# Sheet1.net
KiCad netlist of a schematic drawn in Altium Designer
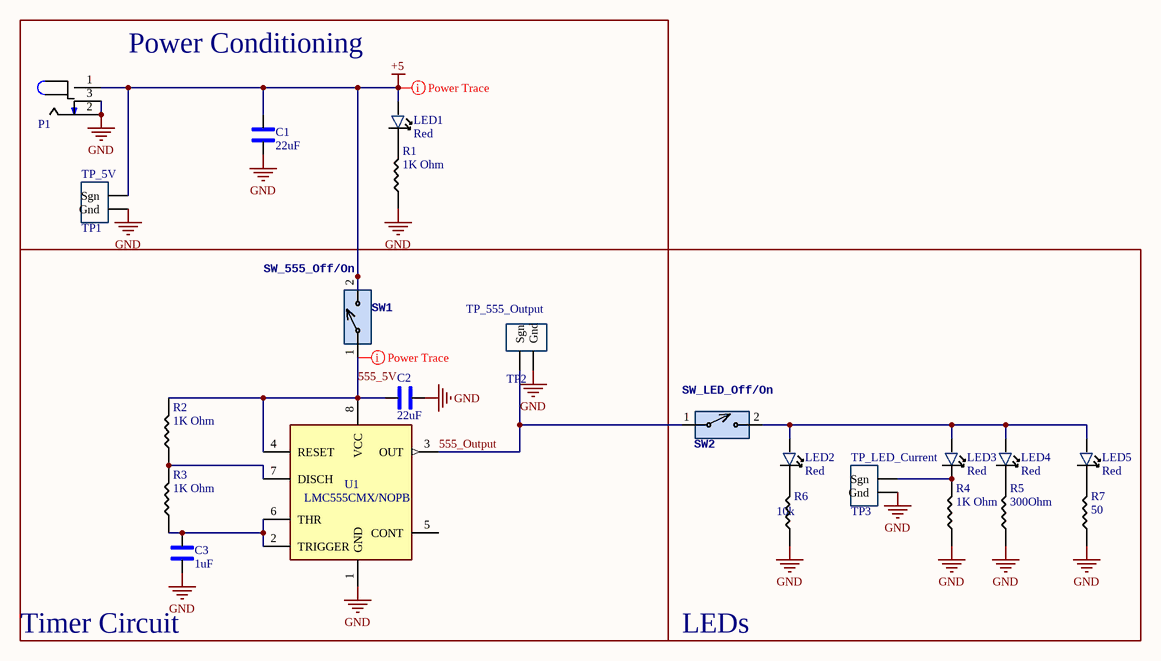
[diagram p0: Sheet1.SchDoc]

(export (version "E")
  (design (tool "Eeschema 10.0.6"))
  (components
    (comp (ref "C1")
      (value "22uF")
      (footprint "1206_Passive_Capacitor")
      (description "22uF ±10% 25V X5R 1206 Multilayer Ceramic Capacitors MLCC - SMD/SMT RoHS")
      (fields (field (name "MFR PART #") "CL31A226KAHNNNE") (field (name "LCSC PART#") "C12891"))
      (libsource (lib "ECEN5730Lib_2023_01_DS") (part "C_22uF_1206"))
    )
    (comp (ref "C2")
      (value "22uF")
      (footprint "1206_Passive_Capacitor")
      (description "22uF ±10% 25V X5R 1206 Multilayer Ceramic Capacitors MLCC - SMD/SMT RoHS")
      (fields (field (name "MFR PART #") "CL31A226KAHNNNE") (field (name "LCSC PART#") "C12891"))
      (libsource (lib "ECEN5730Lib_2023_01_DS") (part "C_22uF_1206"))
    )
    (comp (ref "C3")
      (value "1uF")
      (footprint "1206_Passive_Capacitor")
      (description "MULTILAYER CERAMIC CAPACITORS MLCC - SMD/SMT 1UF 50V 1206 ROHS")
      (fields (field (name "MFR PART #") "CL31B105KBHNNNE") (field (name "LCSC PART#") "C1848"))
      (libsource (lib "ECEN5730Lib_2023_01_DS") (part "C_1uF_1206"))
    )
    (comp (ref "LED1")
      (value "Red")
      (footprint "LED_1206")
      (description "Red 621~631nm 1206 Light Emitting Diodes (LED) RoHS")
      (fields (field (name "MFR PART #") "15-21/R6C-FQ1R1B/2T") (field (name "LCSC PART#") "C93133"))
      (libsource (lib "ECEN5730Lib_2023_01_DS") (part "LED_RED_1206"))
    )
    (comp (ref "LED2")
      (value "Red")
      (footprint "LED_1206")
      (description "Red 621~631nm 1206 Light Emitting Diodes (LED) RoHS")
      (fields (field (name "MFR PART #") "15-21/R6C-FQ1R1B/2T") (field (name "LCSC PART#") "C93133"))
      (libsource (lib "ECEN5730Lib_2023_01_DS") (part "LED_RED_1206"))
    )
    (comp (ref "LED3")
      (value "Red")
      (footprint "LED_1206")
      (description "Red 621~631nm 1206 Light Emitting Diodes (LED) RoHS")
      (fields (field (name "MFR PART #") "15-21/R6C-FQ1R1B/2T") (field (name "LCSC PART#") "C93133"))
      (libsource (lib "ECEN5730Lib_2023_01_DS") (part "LED_RED_1206"))
    )
    (comp (ref "LED4")
      (value "Red")
      (footprint "LED_1206")
      (description "Red 621~631nm 1206 Light Emitting Diodes (LED) RoHS")
      (fields (field (name "MFR PART #") "15-21/R6C-FQ1R1B/2T") (field (name "LCSC PART#") "C93133"))
      (libsource (lib "ECEN5730Lib_2023_01_DS") (part "LED_RED_1206"))
    )
    (comp (ref "LED5")
      (value "Red")
      (footprint "LED_1206")
      (description "Red 621~631nm 1206 Light Emitting Diodes (LED) RoHS")
      (fields (field (name "MFR PART #") "15-21/R6C-FQ1R1B/2T") (field (name "LCSC PART#") "C93133"))
      (libsource (lib "ECEN5730Lib_2023_01_DS") (part "LED_RED_1206"))
    )
    (comp (ref "P1")
      (value "Power Jack")
      (footprint "Power_Jack")
      (description "Power Barrel Connector Jack 2.10mm ID (0.083\"), 5.50mm OD (0.217\") Through Hole, Right Angle")
      (fields (field (name "MFR PART #") "PJ-102A") (field (name "LCSC PART#") "C136744"))
      (libsource (lib "ECEN5730Lib_2023_01_DS") (part "P_Power Jack"))
    )
    (comp (ref "R1")
      (value "1K Ohm")
      (footprint "1206_Passive_Resitor")
      (description "CHIP RESISTOR - SURFACE MOUNT 1KOHMS ±1% 1/4W 1206 ROHS")
      (fields (field (name "MFR PART #") "RNCP1206FTD1K00CT") (field (name "LCSC PART#") "C4410"))
      (libsource (lib "ECEN5730Lib_2023_01_DS") (part "R_1K_1206"))
    )
    (comp (ref "R2")
      (value "1K Ohm")
      (footprint "1206_Passive_Resitor")
      (description "CHIP RESISTOR - SURFACE MOUNT 1KOHMS ±1% 1/4W 1206 ROHS")
      (fields (field (name "MFR PART #") "RNCP1206FTD1K00CT") (field (name "LCSC PART#") "C4410"))
      (libsource (lib "ECEN5730Lib_2023_01_DS") (part "R_1K_1206"))
    )
    (comp (ref "R3")
      (value "1K Ohm")
      (footprint "1206_Passive_Resitor")
      (description "CHIP RESISTOR - SURFACE MOUNT 1KOHMS ±1% 1/4W 1206 ROHS")
      (fields (field (name "MFR PART #") "RNCP1206FTD1K00CT") (field (name "LCSC PART#") "C4410"))
      (libsource (lib "ECEN5730Lib_2023_01_DS") (part "R_1K_1206"))
    )
    (comp (ref "R4")
      (value "1K Ohm")
      (footprint "1206_Passive_Resitor")
      (description "CHIP RESISTOR - SURFACE MOUNT 1KOHMS ±1% 1/4W 1206 ROHS")
      (fields (field (name "MFR PART #") "RNCP1206FTD1K00CT") (field (name "LCSC PART#") "C4410"))
      (libsource (lib "ECEN5730Lib_2023_01_DS") (part "R_1K_1206"))
    )
    (comp (ref "R5")
      (value "300Ohm")
      (footprint "1206_Passive_Resitor")
      (description "CHIP RESISTOR - SURFACE MOUNT 300OHMS ±1% 1/4W 1206 ROHS")
      (fields (field (name "MFR PART #") "1206W4F3000T5E") (field (name "LCSC PART#") "C17887"))
      (libsource (lib "ECEN5730Lib_2023_01_DS") (part "R_300Ohm_1206"))
    )
    (comp (ref "R6")
      (value "10k")
      (footprint "1206_Passive_Resitor")
      (description "CHIP RESISTOR - SURFACE MOUNT 1MOHMS ±1% 1/4W 1206 ROHS")
      (fields (field (name "MFR PART #") "RMCF1206JT1M00") (field (name "LCSC PART#") "C17927"))
      (libsource (lib "ECEN5730Lib_2023_01_DS") (part "R_1M_1206"))
    )
    (comp (ref "R7")
      (value "50")
      (footprint "1206_Passive_Resitor")
      (description "CHIP RESISTOR - SURFACE MOUNT 1MOHMS ±1% 1/4W 1206 ROHS")
      (fields (field (name "MFR PART #") "RMCF1206JT1M00") (field (name "LCSC PART#") "C17927"))
      (libsource (lib "ECEN5730Lib_2023_01_DS") (part "R_1M_1206"))
    )
    (comp (ref "SW1")
      (value "SW_555_Off/On")
      (footprint "2Pin-Header-Conn")
      (description "2Pin Header")
      (fields (field (name "LCSC PART#") "C124375"))
      (libsource (lib "ECEN5730Lib_2023_01_DS") (part "SW_2Pin_100mil_Switch"))
    )
    (comp (ref "SW2")
      (value "SW_LED_Off/On")
      (footprint "2Pin-Header-Conn")
      (description "2Pin Header")
      (fields (field (name "LCSC PART#") "C124375"))
      (libsource (lib "") (part "SW_2Pin_100mil_Switch_1"))
    )
    (comp (ref "TP1")
      (value "TP_5V")
      (footprint "TP10x_Probe")
      (description "Test Point 300 mil centers")
      (libsource (lib "ECEN5730Lib_2023_01_DS") (part "TP_10x_Probe"))
    )
    (comp (ref "TP2")
      (value "TP_555_Output")
      (footprint "TP10x_Probe")
      (description "Test Point 300 mil centers")
      (libsource (lib "") (part "TP_10x_Probe_1"))
    )
    (comp (ref "TP3")
      (value "TP_LED_Current")
      (footprint "TP10x_Probe")
      (description "Test Point 300 mil centers")
      (libsource (lib "ECEN5730Lib_2023_01_DS") (part "TP_10x_Probe"))
    )
    (comp (ref "U1")
      (value "LMC555CMX/NOPB")
      (footprint "TS555IDTTR")
      (description "555 Type, Timer/Oscillator _Single_ IC 3MHz 8-SO")
      (fields (field (name "LCSC PART#") "C90760"))
      (libsource (lib "ECEN5730Lib_2023_01_DS") (part "U_555_Fast"))
    )
  )
  (nets
    (net (code "1") (name "+5") (class "Default")
      (node (ref "C1") (pin "2") (pinfunction "2_2") (pintype "passive"))
      (node (ref "LED1") (pin "1") (pinfunction "1_1") (pintype "passive"))
      (node (ref "P1") (pin "1") (pinfunction "1_1") (pintype "power_in"))
      (node (ref "SW1") (pin "2") (pinfunction "2_2") (pintype "passive"))
      (node (ref "TP1") (pin "1") (pinfunction "Sgn_1") (pintype "passive"))
    )
    (net (code "2") (name "/555_5V") (class "Default")
      (node (ref "C2") (pin "2") (pinfunction "2_2") (pintype "passive"))
      (node (ref "R2") (pin "2") (pinfunction "2_2") (pintype "passive"))
      (node (ref "SW1") (pin "1") (pinfunction "1_1") (pintype "passive"))
      (node (ref "U1") (pin "4") (pinfunction "RESET_4") (pintype "passive"))
      (node (ref "U1") (pin "8") (pinfunction "VCC_8") (pintype "power_in"))
    )
    (net (code "3") (name "/555_Output") (class "Default")
      (node (ref "SW2") (pin "1") (pinfunction "1_1") (pintype "passive"))
      (node (ref "TP2") (pin "1") (pinfunction "Sgn_1") (pintype "passive"))
      (node (ref "U1") (pin "3") (pinfunction "OUT_3") (pintype "output"))
    )
    (net (code "4") (name "GND") (class "Default")
      (node (ref "C1") (pin "1") (pinfunction "1_1") (pintype "passive"))
      (node (ref "C2") (pin "1") (pinfunction "1_1") (pintype "passive"))
      (node (ref "C3") (pin "1") (pinfunction "1_1") (pintype "passive"))
      (node (ref "P1") (pin "2") (pinfunction "2_2") (pintype "power_in"))
      (node (ref "P1") (pin "3") (pinfunction "3_3") (pintype "power_in"))
      (node (ref "R1") (pin "1") (pinfunction "1_1") (pintype "passive"))
      (node (ref "R4") (pin "1") (pinfunction "1_1") (pintype "passive"))
      (node (ref "R5") (pin "1") (pinfunction "1_1") (pintype "passive"))
      (node (ref "R6") (pin "1") (pinfunction "1_1") (pintype "passive"))
      (node (ref "R7") (pin "1") (pinfunction "1_1") (pintype "passive"))
      (node (ref "TP1") (pin "2") (pinfunction "Gnd_2") (pintype "passive"))
      (node (ref "TP2") (pin "2") (pinfunction "Gnd_2") (pintype "passive"))
      (node (ref "TP3") (pin "2") (pinfunction "Gnd_2") (pintype "passive"))
      (node (ref "U1") (pin "1") (pinfunction "GND_1") (pintype "power_in"))
    )
    (net (code "5") (name "Net-(LED1-Pad2)") (class "Default")
      (node (ref "LED1") (pin "2") (pinfunction "2_2") (pintype "passive"))
      (node (ref "R1") (pin "2") (pinfunction "2_2") (pintype "passive"))
    )
    (net (code "6") (name "Net-(LED2-Pad1)") (class "Default")
      (node (ref "LED2") (pin "1") (pinfunction "1_1") (pintype "passive"))
      (node (ref "LED3") (pin "1") (pinfunction "1_1") (pintype "passive"))
      (node (ref "LED4") (pin "1") (pinfunction "1_1") (pintype "passive"))
      (node (ref "LED5") (pin "1") (pinfunction "1_1") (pintype "passive"))
      (node (ref "SW2") (pin "2") (pinfunction "2_2") (pintype "passive"))
    )
    (net (code "7") (name "Net-(LED2-Pad2)") (class "Default")
      (node (ref "LED2") (pin "2") (pinfunction "2_2") (pintype "passive"))
      (node (ref "R6") (pin "2") (pinfunction "2_2") (pintype "passive"))
    )
    (net (code "8") (name "Net-(LED4-Pad2)") (class "Default")
      (node (ref "LED4") (pin "2") (pinfunction "2_2") (pintype "passive"))
      (node (ref "R5") (pin "2") (pinfunction "2_2") (pintype "passive"))
    )
    (net (code "9") (name "Net-(LED5-Pad2)") (class "Default")
      (node (ref "LED5") (pin "2") (pinfunction "2_2") (pintype "passive"))
      (node (ref "R7") (pin "2") (pinfunction "2_2") (pintype "passive"))
    )
    (net (code "10") (name "Net-(TP3-Sgn)") (class "Default")
      (node (ref "LED3") (pin "2") (pinfunction "2_2") (pintype "passive"))
      (node (ref "R4") (pin "2") (pinfunction "2_2") (pintype "passive"))
      (node (ref "TP3") (pin "1") (pinfunction "Sgn_1") (pintype "passive"))
    )
    (net (code "11") (name "Net-(U1-DISCH)") (class "Default")
      (node (ref "R2") (pin "1") (pinfunction "1_1") (pintype "passive"))
      (node (ref "R3") (pin "2") (pinfunction "2_2") (pintype "passive"))
      (node (ref "U1") (pin "7") (pinfunction "DISCH_7") (pintype "passive"))
    )
    (net (code "12") (name "Net-(U1-THR)") (class "Default")
      (node (ref "C3") (pin "2") (pinfunction "2_2") (pintype "passive"))
      (node (ref "R3") (pin "1") (pinfunction "1_1") (pintype "passive"))
      (node (ref "U1") (pin "2") (pinfunction "TRIGGER_2") (pintype "passive"))
      (node (ref "U1") (pin "6") (pinfunction "THR_6") (pintype "passive"))
    )
    (net (code "13") (name "unconnected-(U1-CONT-Pad5)") (class "Default")
      (node (ref "U1") (pin "5") (pinfunction "CONT_5") (pintype "passive"))
    )
  )
)
